# SCH.net
KiCad netlist of a schematic drawn in Altium Designer
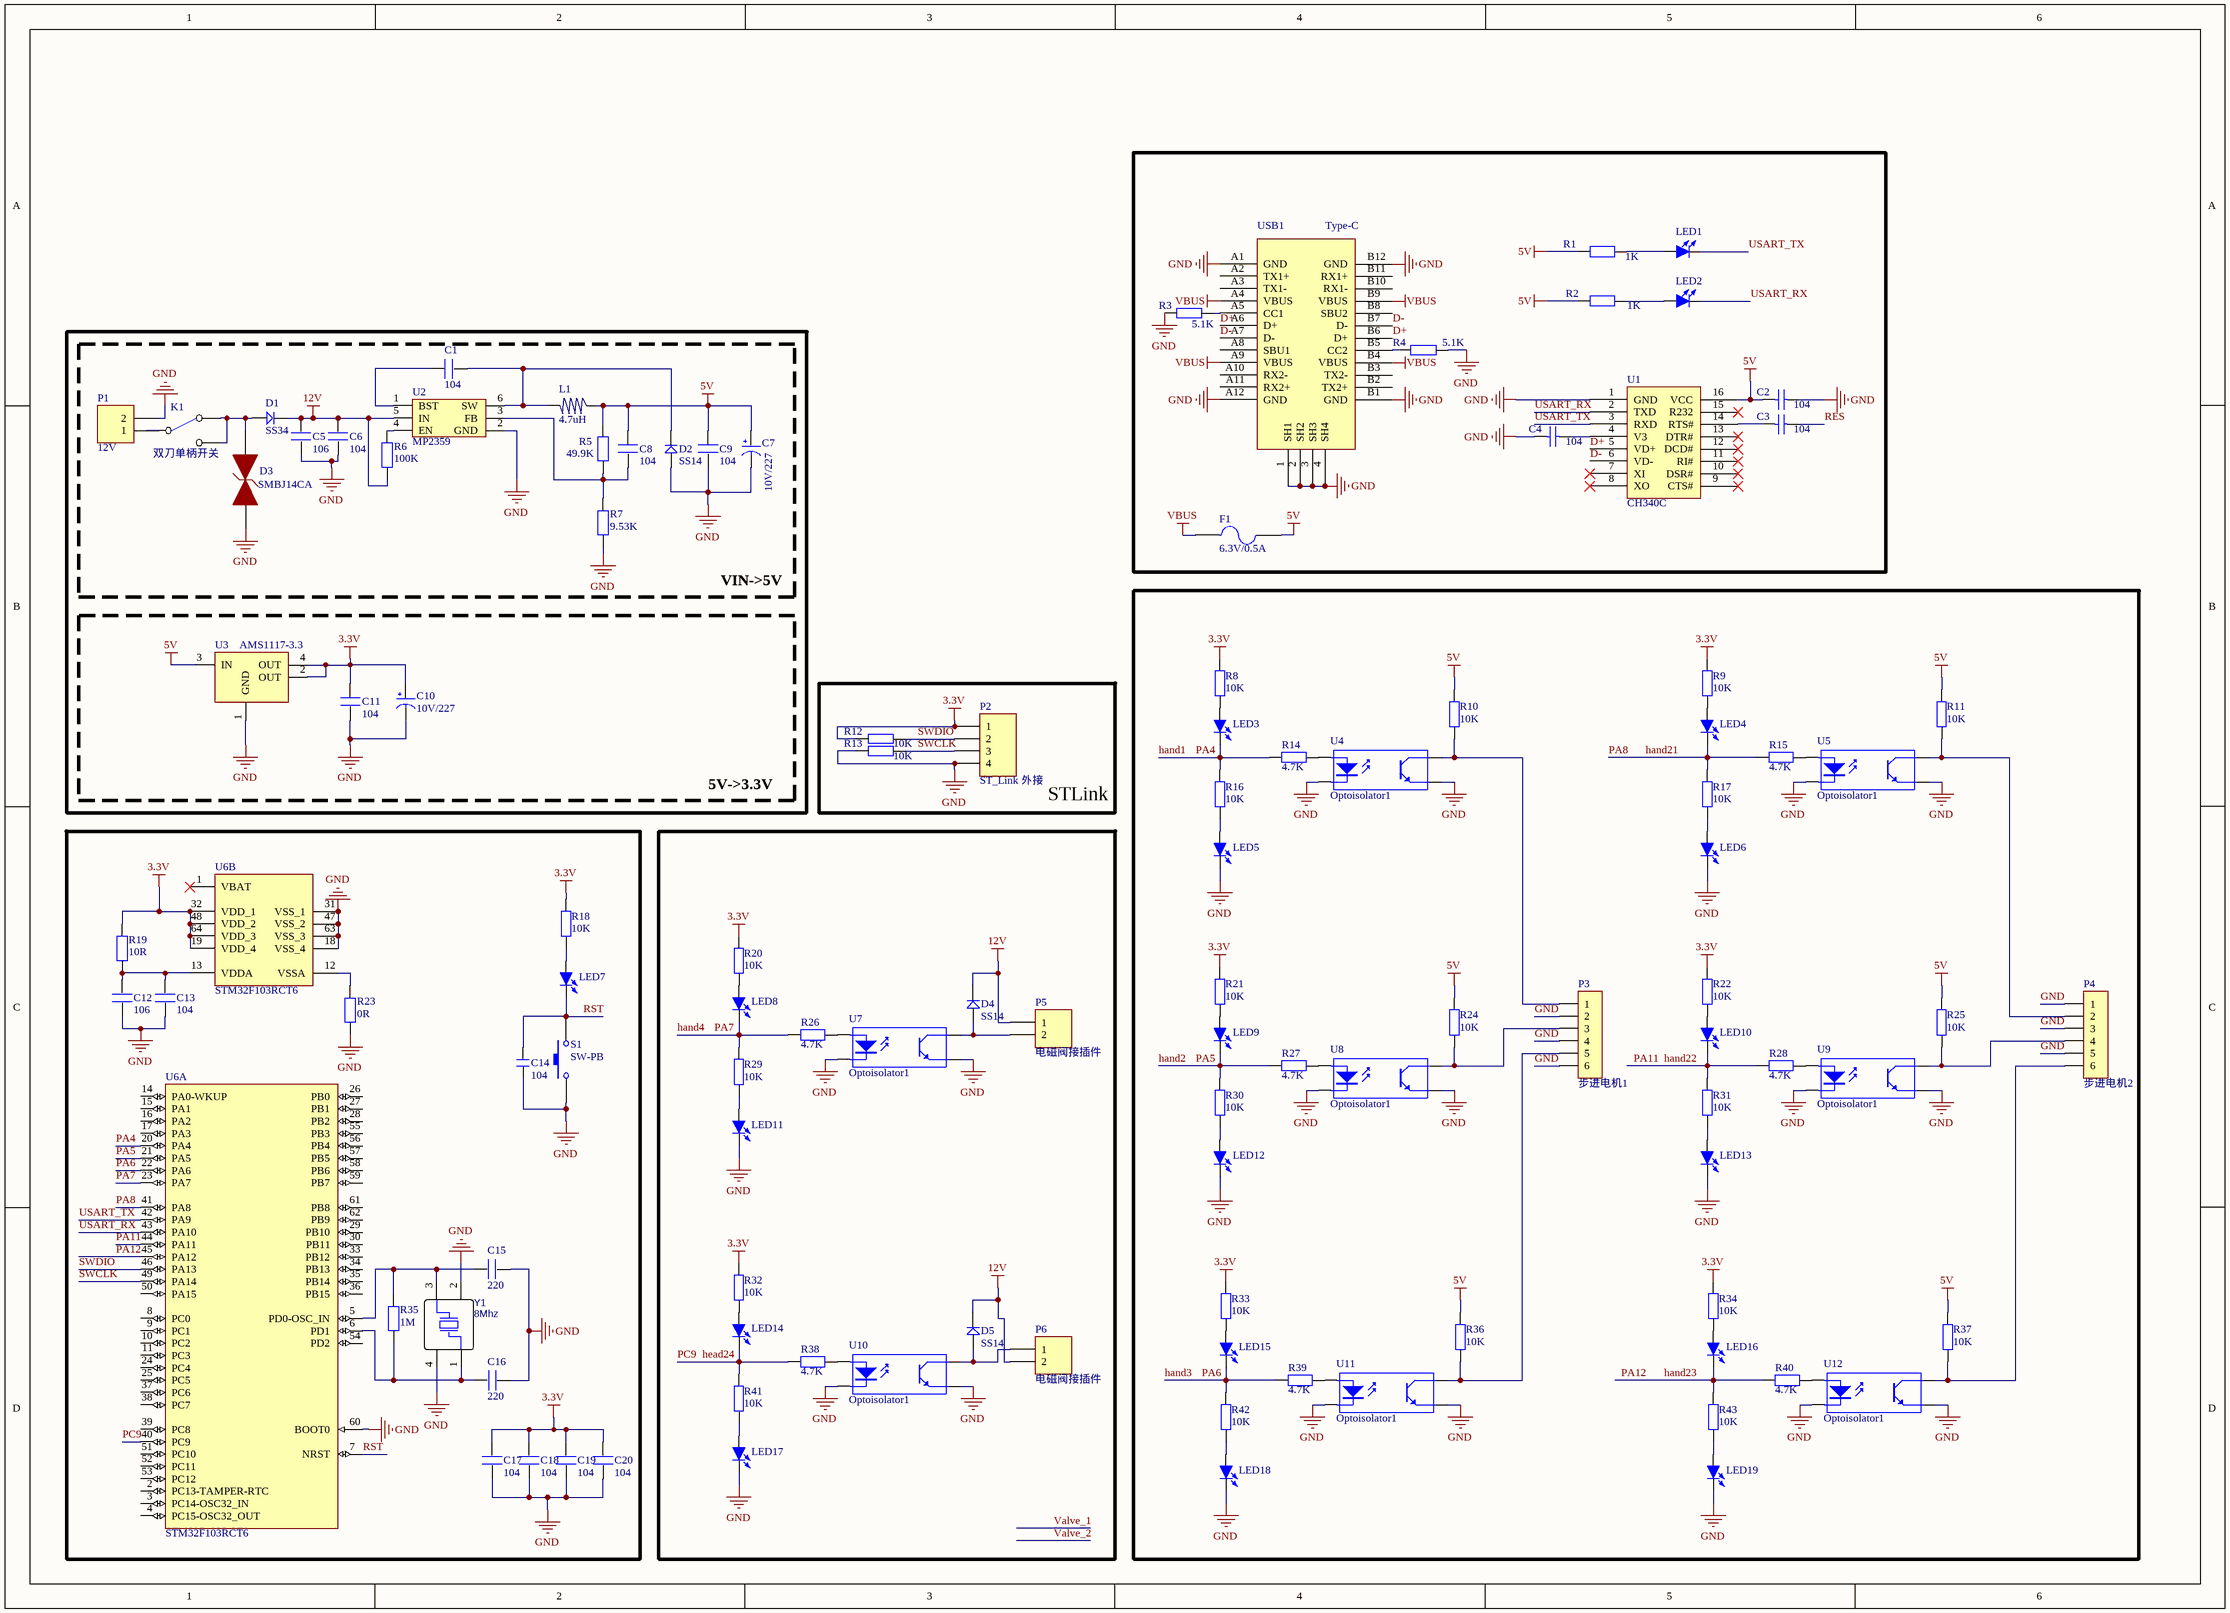
[diagram p0: SCH.SchDoc]

(export (version "E")
  (design (tool "Eeschema 10.0.6"))
  (components
    (comp (ref "C1") (value "104") (footprint "C 0805_L") (libsource (lib "EXPLORER") (part "C")))
    (comp (ref "C2")
      (value "104")
      (footprint "C 0805_L")
      (description "Capacitor")
      (fields (field (name "PUBLISHER") "Altium Limited"))
      (libsource (lib "Miscellaneous Devices") (part "Cap"))
    )
    (comp (ref "C3")
      (value "104")
      (footprint "C 0805_L")
      (description "Capacitor")
      (fields (field (name "PUBLISHER") "Altium Limited"))
      (libsource (lib "Miscellaneous Devices") (part "Cap"))
    )
    (comp (ref "C4")
      (value "104")
      (footprint "C 0805_L")
      (description "Capacitor")
      (fields (field (name "PUBLISHER") "Altium Limited"))
      (libsource (lib "Miscellaneous Devices") (part "Cap"))
    )
    (comp (ref "C5") (value "106") (footprint "C 0805_L") (libsource (lib "EXPLORER") (part "C")))
    (comp (ref "C6") (value "104") (footprint "C 0805_L") (libsource (lib "EXPLORER") (part "C")))
    (comp (ref "C7") (value "10V/227") (footprint "CM D(6.3*7.7)") (libsource (lib "EXPLORER") (part "CAP")))
    (comp (ref "C8") (value "104") (footprint "C 0805_L") (libsource (lib "EXPLORER") (part "C")))
    (comp (ref "C9") (value "104") (footprint "C 0805_L") (libsource (lib "EXPLORER") (part "C")))
    (comp (ref "C10") (value "10V/227") (footprint "CM D(6.3*7.7)") (libsource (lib "EXPLORER") (part "CAP")))
    (comp (ref "C11") (value "104") (footprint "C 0805_L") (libsource (lib "EXPLORER") (part "C")))
    (comp (ref "C12") (value "106") (footprint "C 0805_L") (libsource (lib "EXPLORER") (part "C")))
    (comp (ref "C13") (value "104") (footprint "C 0805_L") (libsource (lib "EXPLORER") (part "C")))
    (comp (ref "C14")
      (value "104")
      (footprint "C 0805_L")
      (description "贴片电容")
      (libsource (lib "0.1 - 电阻-电容-电感") (part "C"))
    )
    (comp (ref "C15") (value "220") (footprint "C 0805_L") (libsource (lib "EXPLORER") (part "C")))
    (comp (ref "C16") (value "220") (footprint "C 0805_L") (libsource (lib "EXPLORER") (part "C")))
    (comp (ref "C17") (value "104") (footprint "C 0805_L") (libsource (lib "EXPLORER") (part "C")))
    (comp (ref "C18") (value "104") (footprint "C 0805_L") (libsource (lib "EXPLORER") (part "C")))
    (comp (ref "C19") (value "104") (footprint "C 0805_L") (libsource (lib "EXPLORER") (part "C")))
    (comp (ref "C20") (value "104") (footprint "C 0805_L") (libsource (lib "EXPLORER") (part "C")))
    (comp (ref "D1") (value "SS34") (footprint "SMA") (libsource (lib "EXPLORER") (part "D")))
    (comp (ref "D2") (value "SS14") (footprint "SMA") (libsource (lib "EXPLORER") (part "D")))
    (comp (ref "D3")
      (value "SMBJ14CA")
      (footprint "SMB/DO214AA")
      (libsource (lib "MyPcbLib") (part "SMBJ28CA"))
    )
    (comp (ref "D4") (value "SS14") (footprint "SMA") (libsource (lib "EXPLORER") (part "D")))
    (comp (ref "D5") (value "SS14") (footprint "SMA") (libsource (lib "EXPLORER") (part "D")))
    (comp (ref "F1")
      (value "6.3V/0.5A")
      (footprint "C 0805_L")
      (description "Fuse")
      (fields (field (name "PUBLISHER") "Altium Limited"))
      (libsource (lib "Miscellaneous Devices") (part "Fuse 2"))
    )
    (comp (ref "K1") (value "双刀单柄开关") (footprint "SS-12D10") (libsource (lib "k-开关") (part "双刀单柄开关")))
    (comp (ref "L1") (value "4.7uH") (footprint "CDRH74") (libsource (lib "EXPLORER") (part "L")))
    (comp (ref "LED1")
      (value "~")
      (footprint "LED 0805R")
      (description "贴片LED")
      (fields (field (name "版权归属") "封装库来自淘宝 ID：黄晶宝石"))
      (libsource (lib "0.3 - LED发光二极管") (part "LED-SMD"))
    )
    (comp (ref "LED2")
      (value "~")
      (footprint "LED 0805R")
      (description "贴片LED")
      (fields (field (name "版权归属") "封装库来自淘宝 ID：黄晶宝石"))
      (libsource (lib "0.3 - LED发光二极管") (part "LED-SMD"))
    )
    (comp (ref "LED3")
      (value "~")
      (footprint "LED 0805R")
      (description "贴片LED")
      (fields (field (name "版权归属") "封装库来自淘宝 ID：黄晶宝石"))
      (libsource (lib "0.3 - LED发光二极管") (part "LED-SMD"))
    )
    (comp (ref "LED4")
      (value "~")
      (footprint "LED 0805R")
      (description "贴片LED")
      (fields (field (name "版权归属") "封装库来自淘宝 ID：黄晶宝石"))
      (libsource (lib "0.3 - LED发光二极管") (part "LED-SMD"))
    )
    (comp (ref "LED5")
      (value "~")
      (footprint "LED 0805R")
      (description "贴片LED")
      (fields (field (name "版权归属") "封装库来自淘宝 ID：黄晶宝石"))
      (libsource (lib "0.3 - LED发光二极管") (part "LED-SMD"))
    )
    (comp (ref "LED6")
      (value "~")
      (footprint "LED 0805R")
      (description "贴片LED")
      (fields (field (name "版权归属") "封装库来自淘宝 ID：黄晶宝石"))
      (libsource (lib "0.3 - LED发光二极管") (part "LED-SMD"))
    )
    (comp (ref "LED7")
      (value "~")
      (footprint "LED 0805R")
      (description "贴片LED")
      (fields (field (name "版权归属") "封装库来自淘宝 ID：黄晶宝石"))
      (libsource (lib "0.3 - LED发光二极管") (part "LED-SMD"))
    )
    (comp (ref "LED8")
      (value "~")
      (footprint "LED 0805R")
      (description "贴片LED")
      (fields (field (name "版权归属") "封装库来自淘宝 ID：黄晶宝石"))
      (libsource (lib "0.3 - LED发光二极管") (part "LED-SMD"))
    )
    (comp (ref "LED9")
      (value "~")
      (footprint "LED 0805R")
      (description "贴片LED")
      (fields (field (name "版权归属") "封装库来自淘宝 ID：黄晶宝石"))
      (libsource (lib "0.3 - LED发光二极管") (part "LED-SMD"))
    )
    (comp (ref "LED10")
      (value "~")
      (footprint "LED 0805R")
      (description "贴片LED")
      (fields (field (name "版权归属") "封装库来自淘宝 ID：黄晶宝石"))
      (libsource (lib "0.3 - LED发光二极管") (part "LED-SMD"))
    )
    (comp (ref "LED11")
      (value "~")
      (footprint "LED 0805R")
      (description "贴片LED")
      (fields (field (name "版权归属") "封装库来自淘宝 ID：黄晶宝石"))
      (libsource (lib "0.3 - LED发光二极管") (part "LED-SMD"))
    )
    (comp (ref "LED12")
      (value "~")
      (footprint "LED 0805R")
      (description "贴片LED")
      (fields (field (name "版权归属") "封装库来自淘宝 ID：黄晶宝石"))
      (libsource (lib "0.3 - LED发光二极管") (part "LED-SMD"))
    )
    (comp (ref "LED13")
      (value "~")
      (footprint "LED 0805R")
      (description "贴片LED")
      (fields (field (name "版权归属") "封装库来自淘宝 ID：黄晶宝石"))
      (libsource (lib "0.3 - LED发光二极管") (part "LED-SMD"))
    )
    (comp (ref "LED14")
      (value "~")
      (footprint "LED 0805R")
      (description "贴片LED")
      (fields (field (name "版权归属") "封装库来自淘宝 ID：黄晶宝石"))
      (libsource (lib "0.3 - LED发光二极管") (part "LED-SMD"))
    )
    (comp (ref "LED15")
      (value "~")
      (footprint "LED 0805R")
      (description "贴片LED")
      (fields (field (name "版权归属") "封装库来自淘宝 ID：黄晶宝石"))
      (libsource (lib "0.3 - LED发光二极管") (part "LED-SMD"))
    )
    (comp (ref "LED16")
      (value "~")
      (footprint "LED 0805R")
      (description "贴片LED")
      (fields (field (name "版权归属") "封装库来自淘宝 ID：黄晶宝石"))
      (libsource (lib "0.3 - LED发光二极管") (part "LED-SMD"))
    )
    (comp (ref "LED17")
      (value "~")
      (footprint "LED 0805R")
      (description "贴片LED")
      (fields (field (name "版权归属") "封装库来自淘宝 ID：黄晶宝石"))
      (libsource (lib "0.3 - LED发光二极管") (part "LED-SMD"))
    )
    (comp (ref "LED18")
      (value "~")
      (footprint "LED 0805R")
      (description "贴片LED")
      (fields (field (name "版权归属") "封装库来自淘宝 ID：黄晶宝石"))
      (libsource (lib "0.3 - LED发光二极管") (part "LED-SMD"))
    )
    (comp (ref "LED19")
      (value "~")
      (footprint "LED 0805R")
      (description "贴片LED")
      (fields (field (name "版权归属") "封装库来自淘宝 ID：黄晶宝石"))
      (libsource (lib "0.3 - LED发光二极管") (part "LED-SMD"))
    )
    (comp (ref "P1")
      (value "12V")
      (footprint "KF128-5.08-2P")
      (description "12-24V")
      (fields (field (name "PUBLISHER") "Altium Limited"))
      (libsource (lib "EXPLORER") (part "Header 2"))
    )
    (comp (ref "P2")
      (value "ST_Link 外接")
      (footprint "HDR1X4")
      (description "Header, 4-Pin")
      (fields (field (name "PUBLISHER") "Altium Limited"))
      (libsource (lib "Miscellaneous Connectors") (part "Header 4"))
    )
    (comp (ref "P3")
      (value "步进电机1")
      (footprint "KF128-5.08-6P")
      (description "6P接插件")
      (libsource (lib "18 - 接插件-脚距2.54mm (100mil) ") (part "Header 6"))
    )
    (comp (ref "P4")
      (value "步进电机2")
      (footprint "KF128-5.08-6P")
      (description "6P接插件")
      (libsource (lib "18 - 接插件-脚距2.54mm (100mil) ") (part "Header 6"))
    )
    (comp (ref "P5")
      (value "电磁阀接插件")
      (footprint "KF128-5.08-2P")
      (description "Header, 2-Pin")
      (fields (field (name "PUBLISHER") "Altium Limited"))
      (libsource (lib "Miscellaneous Connectors") (part "MHDR1X2"))
    )
    (comp (ref "P6")
      (value "电磁阀接插件")
      (footprint "KF128-5.08-2P")
      (description "Header, 2-Pin")
      (fields (field (name "PUBLISHER") "Altium Limited"))
      (libsource (lib "Miscellaneous Connectors") (part "MHDR1X2"))
    )
    (comp (ref "R1")
      (value "1K")
      (footprint "R 0805_L")
      (description "Resistor")
      (fields (field (name "PUBLISHER") "Altium Limited"))
      (libsource (lib "") (part "Res2_2"))
    )
    (comp (ref "R2")
      (value "1K")
      (footprint "R 0805_L")
      (description "Resistor")
      (fields (field (name "PUBLISHER") "Altium Limited"))
      (libsource (lib "") (part "Res2_2"))
    )
    (comp (ref "R3") (value "5.1K") (footprint "R 0805_L") (libsource (lib "EXPLORER") (part "R")))
    (comp (ref "R4") (value "5.1K") (footprint "R 0805_L") (libsource (lib "EXPLORER") (part "R")))
    (comp (ref "R5") (value "49.9K") (footprint "R 0805_L") (libsource (lib "EXPLORER") (part "R")))
    (comp (ref "R6") (value "100K") (footprint "R 0805_L") (libsource (lib "EXPLORER") (part "R")))
    (comp (ref "R7") (value "9.53K") (footprint "R 0805_L") (libsource (lib "EXPLORER") (part "R")))
    (comp (ref "R8")
      (value "10K")
      (footprint "R 0805_L")
      (description "Resistor")
      (fields (field (name "PUBLISHER") "Altium Limited"))
      (libsource (lib "") (part "Res2_1"))
    )
    (comp (ref "R9")
      (value "10K")
      (footprint "R 0805_L")
      (description "Resistor")
      (fields (field (name "PUBLISHER") "Altium Limited"))
      (libsource (lib "") (part "Res2_1"))
    )
    (comp (ref "R10")
      (value "10K")
      (footprint "R 0805_L")
      (description "Resistor")
      (fields (field (name "PUBLISHER") "Altium Limited"))
      (libsource (lib "") (part "Res2_1"))
    )
    (comp (ref "R11")
      (value "10K")
      (footprint "R 0805_L")
      (description "Resistor")
      (fields (field (name "PUBLISHER") "Altium Limited"))
      (libsource (lib "") (part "Res2_1"))
    )
    (comp (ref "R12") (value "10K") (footprint "R 0805_L") (libsource (lib "EXPLORER") (part "R")))
    (comp (ref "R13") (value "10K") (footprint "R 0805_L") (libsource (lib "EXPLORER") (part "R")))
    (comp (ref "R14")
      (value "4.7K")
      (footprint "R 0805_L")
      (description "Resistor")
      (fields (field (name "PUBLISHER") "Altium Limited"))
      (libsource (lib "Miscellaneous Devices") (part "Res2"))
    )
    (comp (ref "R15")
      (value "4.7K")
      (footprint "R 0805_L")
      (description "Resistor")
      (fields (field (name "PUBLISHER") "Altium Limited"))
      (libsource (lib "Miscellaneous Devices") (part "Res2"))
    )
    (comp (ref "R16")
      (value "10K")
      (footprint "R 0805_L")
      (description "Resistor")
      (fields (field (name "PUBLISHER") "Altium Limited"))
      (libsource (lib "") (part "Res2_1"))
    )
    (comp (ref "R17")
      (value "10K")
      (footprint "R 0805_L")
      (description "Resistor")
      (fields (field (name "PUBLISHER") "Altium Limited"))
      (libsource (lib "") (part "Res2_1"))
    )
    (comp (ref "R18")
      (value "10K")
      (footprint "R 0805_L")
      (description "Resistor")
      (fields (field (name "PUBLISHER") "Altium Limited"))
      (libsource (lib "") (part "Res2_1"))
    )
    (comp (ref "R19") (value "10R") (footprint "R 0805_L") (libsource (lib "EXPLORER") (part "R")))
    (comp (ref "R20")
      (value "10K")
      (footprint "R 0805_L")
      (description "Resistor")
      (fields (field (name "PUBLISHER") "Altium Limited"))
      (libsource (lib "") (part "Res2_1"))
    )
    (comp (ref "R21")
      (value "10K")
      (footprint "R 0805_L")
      (description "Resistor")
      (fields (field (name "PUBLISHER") "Altium Limited"))
      (libsource (lib "") (part "Res2_1"))
    )
    (comp (ref "R22")
      (value "10K")
      (footprint "R 0805_L")
      (description "Resistor")
      (fields (field (name "PUBLISHER") "Altium Limited"))
      (libsource (lib "") (part "Res2_1"))
    )
    (comp (ref "R23") (value "0R") (footprint "R 0805_L") (libsource (lib "EXPLORER") (part "R")))
    (comp (ref "R24")
      (value "10K")
      (footprint "R 0805_L")
      (description "Resistor")
      (fields (field (name "PUBLISHER") "Altium Limited"))
      (libsource (lib "") (part "Res2_1"))
    )
    (comp (ref "R25")
      (value "10K")
      (footprint "R 0805_L")
      (description "Resistor")
      (fields (field (name "PUBLISHER") "Altium Limited"))
      (libsource (lib "") (part "Res2_1"))
    )
    (comp (ref "R26")
      (value "4.7K")
      (footprint "R 0805_L")
      (description "Resistor")
      (fields (field (name "PUBLISHER") "Altium Limited"))
      (libsource (lib "Miscellaneous Devices") (part "Res2"))
    )
    (comp (ref "R27")
      (value "4.7K")
      (footprint "R 0805_L")
      (description "Resistor")
      (fields (field (name "PUBLISHER") "Altium Limited"))
      (libsource (lib "Miscellaneous Devices") (part "Res2"))
    )
    (comp (ref "R28")
      (value "4.7K")
      (footprint "R 0805_L")
      (description "Resistor")
      (fields (field (name "PUBLISHER") "Altium Limited"))
      (libsource (lib "Miscellaneous Devices") (part "Res2"))
    )
    (comp (ref "R29")
      (value "10K")
      (footprint "R 0805_L")
      (description "Resistor")
      (fields (field (name "PUBLISHER") "Altium Limited"))
      (libsource (lib "") (part "Res2_1"))
    )
    (comp (ref "R30")
      (value "10K")
      (footprint "R 0805_L")
      (description "Resistor")
      (fields (field (name "PUBLISHER") "Altium Limited"))
      (libsource (lib "") (part "Res2_1"))
    )
    (comp (ref "R31")
      (value "10K")
      (footprint "R 0805_L")
      (description "Resistor")
      (fields (field (name "PUBLISHER") "Altium Limited"))
      (libsource (lib "") (part "Res2_1"))
    )
    (comp (ref "R32")
      (value "10K")
      (footprint "R 0805_L")
      (description "Resistor")
      (fields (field (name "PUBLISHER") "Altium Limited"))
      (libsource (lib "") (part "Res2_1"))
    )
    (comp (ref "R33")
      (value "10K")
      (footprint "R 0805_L")
      (description "Resistor")
      (fields (field (name "PUBLISHER") "Altium Limited"))
      (libsource (lib "") (part "Res2_1"))
    )
    (comp (ref "R34")
      (value "10K")
      (footprint "R 0805_L")
      (description "Resistor")
      (fields (field (name "PUBLISHER") "Altium Limited"))
      (libsource (lib "") (part "Res2_1"))
    )
    (comp (ref "R35") (value "1M") (footprint "R 0805_L") (libsource (lib "EXPLORER") (part "R")))
    (comp (ref "R36")
      (value "10K")
      (footprint "R 0805_L")
      (description "Resistor")
      (fields (field (name "PUBLISHER") "Altium Limited"))
      (libsource (lib "") (part "Res2_1"))
    )
    (comp (ref "R37")
      (value "10K")
      (footprint "R 0805_L")
      (description "Resistor")
      (fields (field (name "PUBLISHER") "Altium Limited"))
      (libsource (lib "") (part "Res2_1"))
    )
    (comp (ref "R38")
      (value "4.7K")
      (footprint "R 0805_L")
      (description "Resistor")
      (fields (field (name "PUBLISHER") "Altium Limited"))
      (libsource (lib "Miscellaneous Devices") (part "Res2"))
    )
    (comp (ref "R39")
      (value "4.7K")
      (footprint "R 0805_L")
      (description "Resistor")
      (fields (field (name "PUBLISHER") "Altium Limited"))
      (libsource (lib "Miscellaneous Devices") (part "Res2"))
    )
    (comp (ref "R40")
      (value "4.7K")
      (footprint "R 0805_L")
      (description "Resistor")
      (fields (field (name "PUBLISHER") "Altium Limited"))
      (libsource (lib "Miscellaneous Devices") (part "Res2"))
    )
    (comp (ref "R41")
      (value "10K")
      (footprint "R 0805_L")
      (description "Resistor")
      (fields (field (name "PUBLISHER") "Altium Limited"))
      (libsource (lib "") (part "Res2_1"))
    )
    (comp (ref "R42")
      (value "10K")
      (footprint "R 0805_L")
      (description "Resistor")
      (fields (field (name "PUBLISHER") "Altium Limited"))
      (libsource (lib "") (part "Res2_1"))
    )
    (comp (ref "R43")
      (value "10K")
      (footprint "R 0805_L")
      (description "Resistor")
      (fields (field (name "PUBLISHER") "Altium Limited"))
      (libsource (lib "") (part "Res2_1"))
    )
    (comp (ref "S1")
      (value "SW-PB")
      (footprint "复位按键")
      (description "Switch")
      (fields (field (name "PUBLISHER") "Altium Limited"))
      (libsource (lib "Miscellaneous Devices") (part "SW-PB"))
    )
    (comp (ref "U1") (value "CH340C") (footprint "SOP16") (libsource (lib "Schlib1") (part "CH340G")))
    (comp (ref "U2")
      (value "MP2359")
      (footprint "SOT23-6L")
      (description "DC DC Step Down IC")
      (libsource (lib "EXPLORER") (part "MP2359"))
    )
    (comp (ref "U3")
      (value "AMS1117-3.3")
      (footprint "SOT223_L")
      (libsource (lib "EXPLORER") (part "AMS1117"))
    )
    (comp (ref "U4")
      (value "Optoisolator1")
      (footprint "SOP4-W2.54_M")
      (description "4-Pin Phototransistor Optocoupler")
      (fields (field (name "PUBLISHER") "Altium Limited"))
      (libsource (lib "Miscellaneous Devices") (part "Optoisolator1"))
    )
    (comp (ref "U5")
      (value "Optoisolator1")
      (footprint "SOP4-W2.54_M")
      (description "4-Pin Phototransistor Optocoupler")
      (fields (field (name "PUBLISHER") "Altium Limited"))
      (libsource (lib "Miscellaneous Devices") (part "Optoisolator1"))
    )
    (comp (ref "U6")
      (value "STM32F103RCT6")
      (footprint "LQFP64_N")
      (libsource (lib "2.3 - STM32 F1系列MCU 集成库") (part "STM32F103RCT6"))
    )
    (comp (ref "U7")
      (value "Optoisolator1")
      (footprint "SOP4-W2.54_M")
      (description "4-Pin Phototransistor Optocoupler")
      (fields (field (name "PUBLISHER") "Altium Limited"))
      (libsource (lib "Miscellaneous Devices") (part "Optoisolator1"))
    )
    (comp (ref "U8")
      (value "Optoisolator1")
      (footprint "SOP4-W2.54_M")
      (description "4-Pin Phototransistor Optocoupler")
      (fields (field (name "PUBLISHER") "Altium Limited"))
      (libsource (lib "Miscellaneous Devices") (part "Optoisolator1"))
    )
    (comp (ref "U9")
      (value "Optoisolator1")
      (footprint "SOP4-W2.54_M")
      (description "4-Pin Phototransistor Optocoupler")
      (fields (field (name "PUBLISHER") "Altium Limited"))
      (libsource (lib "Miscellaneous Devices") (part "Optoisolator1"))
    )
    (comp (ref "U10")
      (value "Optoisolator1")
      (footprint "SOP4-W2.54_M")
      (description "4-Pin Phototransistor Optocoupler")
      (fields (field (name "PUBLISHER") "Altium Limited"))
      (libsource (lib "Miscellaneous Devices") (part "Optoisolator1"))
    )
    (comp (ref "U11")
      (value "Optoisolator1")
      (footprint "SOP4-W2.54_M")
      (description "4-Pin Phototransistor Optocoupler")
      (fields (field (name "PUBLISHER") "Altium Limited"))
      (libsource (lib "Miscellaneous Devices") (part "Optoisolator1"))
    )
    (comp (ref "U12")
      (value "Optoisolator1")
      (footprint "SOP4-W2.54_M")
      (description "4-Pin Phototransistor Optocoupler")
      (fields (field (name "PUBLISHER") "Altium Limited"))
      (libsource (lib "Miscellaneous Devices") (part "Optoisolator1"))
    )
    (comp (ref "USB1")
      (value "Type-C")
      (footprint "USBTypeC-16P")
      (libsource (lib "MyPcbLib") (part "USB-Type-C-TOP"))
    )
    (comp (ref "Y1")
      (value "8Mhz")
      (footprint "OSC 5032-4P")
      (fields
        (field (name "BOM_MANUFACTURER PART") "X322516MLB4SI")
        (field (name "BOM_SUPPLIER PART") "C13738")
      )
      (libsource (lib "EXPLORER") (part "Y"))
    )
  )
  (nets
    (net (code "1") (name "/D+") (class "Default")
      (node (ref "U1") (pin "5") (pinfunction "VD+_5") (pintype "passive"))
      (node (ref "USB1") (pin "A6") (pinfunction "D+_A6") (pintype "passive"))
      (node (ref "USB1") (pin "B6") (pinfunction "D+_B6") (pintype "passive"))
    )
    (net (code "2") (name "/D-") (class "Default")
      (node (ref "U1") (pin "6") (pinfunction "VD-_6") (pintype "passive"))
      (node (ref "USB1") (pin "A7") (pinfunction "D-_A7") (pintype "passive"))
      (node (ref "USB1") (pin "B7") (pinfunction "D-_B7") (pintype "passive"))
    )
    (net (code "3") (name "/PA4") (class "Default")
      (node (ref "LED3") (pin "2") (pinfunction "K_2") (pintype "passive"))
      (node (ref "R14") (pin "1") (pinfunction "1_1") (pintype "passive"))
      (node (ref "R16") (pin "1") (pinfunction "1_1") (pintype "passive"))
      (node (ref "U6") (pin "20") (pinfunction "PA4_20") (pintype "bidirectional"))
    )
    (net (code "4") (name "/PA5") (class "Default")
      (node (ref "LED9") (pin "2") (pinfunction "K_2") (pintype "passive"))
      (node (ref "R27") (pin "1") (pinfunction "1_1") (pintype "passive"))
      (node (ref "R30") (pin "1") (pinfunction "1_1") (pintype "passive"))
      (node (ref "U6") (pin "21") (pinfunction "PA5_21") (pintype "bidirectional"))
    )
    (net (code "5") (name "/PA6") (class "Default")
      (node (ref "LED15") (pin "2") (pinfunction "K_2") (pintype "passive"))
      (node (ref "R39") (pin "1") (pinfunction "1_1") (pintype "passive"))
      (node (ref "R42") (pin "1") (pinfunction "1_1") (pintype "passive"))
      (node (ref "U6") (pin "22") (pinfunction "PA6_22") (pintype "bidirectional"))
    )
    (net (code "6") (name "/PA7") (class "Default")
      (node (ref "LED8") (pin "2") (pinfunction "K_2") (pintype "passive"))
      (node (ref "R26") (pin "1") (pinfunction "1_1") (pintype "passive"))
      (node (ref "R29") (pin "1") (pinfunction "1_1") (pintype "passive"))
      (node (ref "U6") (pin "23") (pinfunction "PA7_23") (pintype "bidirectional"))
    )
    (net (code "7") (name "/PA8") (class "Default")
      (node (ref "LED4") (pin "2") (pinfunction "K_2") (pintype "passive"))
      (node (ref "R15") (pin "1") (pinfunction "1_1") (pintype "passive"))
      (node (ref "R17") (pin "1") (pinfunction "1_1") (pintype "passive"))
      (node (ref "U6") (pin "41") (pinfunction "PA8_41") (pintype "bidirectional"))
    )
    (net (code "8") (name "/PA11") (class "Default")
      (node (ref "LED10") (pin "2") (pinfunction "K_2") (pintype "passive"))
      (node (ref "R28") (pin "1") (pinfunction "1_1") (pintype "passive"))
      (node (ref "R31") (pin "1") (pinfunction "1_1") (pintype "passive"))
      (node (ref "U6") (pin "44") (pinfunction "PA11_44") (pintype "bidirectional"))
    )
    (net (code "9") (name "/PA12") (class "Default")
      (node (ref "LED16") (pin "2") (pinfunction "K_2") (pintype "passive"))
      (node (ref "R40") (pin "1") (pinfunction "1_1") (pintype "passive"))
      (node (ref "R43") (pin "1") (pinfunction "1_1") (pintype "passive"))
      (node (ref "U6") (pin "45") (pinfunction "PA12_45") (pintype "bidirectional"))
    )
    (net (code "10") (name "/PC9") (class "Default")
      (node (ref "LED14") (pin "2") (pinfunction "K_2") (pintype "passive"))
      (node (ref "R38") (pin "1") (pinfunction "1_1") (pintype "passive"))
      (node (ref "R41") (pin "1") (pinfunction "1_1") (pintype "passive"))
      (node (ref "U6") (pin "40") (pinfunction "PC9_40") (pintype "bidirectional"))
    )
    (net (code "11") (name "/RES") (class "Default")
      (node (ref "C3") (pin "1") (pinfunction "1_1") (pintype "passive"))
    )
    (net (code "12") (name "/RST") (class "Default")
      (node (ref "C14") (pin "2") (pinfunction "2_2") (pintype "passive"))
      (node (ref "LED7") (pin "2") (pinfunction "K_2") (pintype "passive"))
      (node (ref "S1") (pin "2") (pinfunction "2_2") (pintype "passive"))
      (node (ref "U6") (pin "7") (pinfunction "NRST_7") (pintype "bidirectional"))
    )
    (net (code "13") (name "/SWCLK") (class "Default")
      (node (ref "P2") (pin "3") (pinfunction "3_3") (pintype "passive"))
      (node (ref "R13") (pin "1") (pintype "passive"))
      (node (ref "U6") (pin "49") (pinfunction "PA14_49") (pintype "bidirectional"))
    )
    (net (code "14") (name "/SWDIO") (class "Default")
      (node (ref "P2") (pin "2") (pinfunction "2_2") (pintype "passive"))
      (node (ref "R12") (pin "1") (pintype "passive"))
      (node (ref "U6") (pin "46") (pinfunction "PA13_46") (pintype "bidirectional"))
    )
    (net (code "15") (name "/USART_RX") (class "Default")
      (node (ref "LED2") (pin "2") (pinfunction "K_2") (pintype "passive"))
      (node (ref "U1") (pin "2") (pinfunction "TXD_2") (pintype "passive"))
      (node (ref "U6") (pin "43") (pinfunction "PA10_43") (pintype "bidirectional"))
    )
    (net (code "16") (name "/USART_TX") (class "Default")
      (node (ref "LED1") (pin "2") (pinfunction "K_2") (pintype "passive"))
      (node (ref "U1") (pin "3") (pinfunction "RXD_3") (pintype "passive"))
      (node (ref "U6") (pin "42") (pinfunction "PA9_42") (pintype "bidirectional"))
    )
    (net (code "19") (name "3.3V") (class "Default")
      (node (ref "C10") (pin "1") (pinfunction "VCC_1") (pintype "passive"))
      (node (ref "C11") (pin "2") (pintype "passive"))
      (node (ref "C17") (pin "2") (pintype "passive"))
      (node (ref "C18") (pin "2") (pintype "passive"))
      (node (ref "C19") (pin "2") (pintype "passive"))
      (node (ref "C20") (pin "2") (pintype "passive"))
      (node (ref "P2") (pin "1") (pinfunction "1_1") (pintype "passive"))
      (node (ref "R12") (pin "2") (pintype "passive"))
      (node (ref "R18") (pin "1") (pinfunction "1_1") (pintype "passive"))
      (node (ref "R19") (pin "2") (pintype "passive"))
      (node (ref "R20") (pin "1") (pinfunction "1_1") (pintype "passive"))
      (node (ref "R21") (pin "1") (pinfunction "1_1") (pintype "passive"))
      (node (ref "R22") (pin "1") (pinfunction "1_1") (pintype "passive"))
      (node (ref "R32") (pin "1") (pinfunction "1_1") (pintype "passive"))
      (node (ref "R33") (pin "1") (pinfunction "1_1") (pintype "passive"))
      (node (ref "R34") (pin "1") (pinfunction "1_1") (pintype "passive"))
      (node (ref "R8") (pin "1") (pinfunction "1_1") (pintype "passive"))
      (node (ref "R9") (pin "1") (pinfunction "1_1") (pintype "passive"))
      (node (ref "U3") (pin "2") (pinfunction "OUT_2") (pintype "passive"))
      (node (ref "U3") (pin "4") (pinfunction "OUT_4") (pintype "passive"))
      (node (ref "U6") (pin "19") (pinfunction "VDD_4_19") (pintype "power_in"))
      (node (ref "U6") (pin "32") (pinfunction "VDD_1_32") (pintype "power_in"))
      (node (ref "U6") (pin "48") (pinfunction "VDD_2_48") (pintype "power_in"))
      (node (ref "U6") (pin "64") (pinfunction "VDD_3_64") (pintype "power_in"))
    )
    (net (code "20") (name "5V") (class "Default")
      (node (ref "C2") (pin "2") (pinfunction "2_2") (pintype "passive"))
      (node (ref "C7") (pin "1") (pinfunction "VCC_1") (pintype "passive"))
      (node (ref "C8") (pin "2") (pintype "passive"))
      (node (ref "C9") (pin "2") (pintype "passive"))
      (node (ref "F1") (pin "2") (pinfunction "2_2") (pintype "passive"))
      (node (ref "L1") (pin "1") (pintype "passive"))
      (node (ref "R1") (pin "2") (pinfunction "2_2") (pintype "passive"))
      (node (ref "R10") (pin "1") (pinfunction "1_1") (pintype "passive"))
      (node (ref "R11") (pin "1") (pinfunction "1_1") (pintype "passive"))
      (node (ref "R2") (pin "2") (pinfunction "2_2") (pintype "passive"))
      (node (ref "R24") (pin "1") (pinfunction "1_1") (pintype "passive"))
      (node (ref "R25") (pin "1") (pinfunction "1_1") (pintype "passive"))
      (node (ref "R36") (pin "1") (pinfunction "1_1") (pintype "passive"))
      (node (ref "R37") (pin "1") (pinfunction "1_1") (pintype "passive"))
      (node (ref "R5") (pin "2") (pintype "passive"))
      (node (ref "U1") (pin "16") (pinfunction "VCC_16") (pintype "passive"))
      (node (ref "U3") (pin "3") (pinfunction "IN_3") (pintype "passive"))
    )
    (net (code "21") (name "12V") (class "Default")
      (node (ref "C5") (pin "2") (pintype "passive"))
      (node (ref "C6") (pin "2") (pintype "passive"))
      (node (ref "D1") (pin "2") (pintype "passive"))
      (node (ref "D4") (pin "2") (pintype "passive"))
      (node (ref "D5") (pin "2") (pintype "passive"))
      (node (ref "P5") (pin "1") (pinfunction "1_1") (pintype "passive"))
      (node (ref "P6") (pin "2") (pinfunction "2_2") (pintype "passive"))
      (node (ref "R6") (pin "2") (pintype "passive"))
      (node (ref "U2") (pin "5") (pinfunction "IN_5") (pintype "passive"))
    )
    (net (code "22") (name "GND") (class "Default")
      (node (ref "C10") (pin "2") (pinfunction "GND_2") (pintype "passive"))
      (node (ref "C11") (pin "1") (pintype "passive"))
      (node (ref "C12") (pin "2") (pintype "passive"))
      (node (ref "C13") (pin "2") (pintype "passive"))
      (node (ref "C14") (pin "1") (pinfunction "1_1") (pintype "passive"))
      (node (ref "C15") (pin "2") (pintype "passive"))
      (node (ref "C16") (pin "1") (pintype "passive"))
      (node (ref "C17") (pin "1") (pintype "passive"))
      (node (ref "C18") (pin "1") (pintype "passive"))
      (node (ref "C19") (pin "1") (pintype "passive"))
      (node (ref "C2") (pin "1") (pinfunction "1_1") (pintype "passive"))
      (node (ref "C20") (pin "1") (pintype "passive"))
      (node (ref "C4") (pin "2") (pinfunction "2_2") (pintype "passive"))
      (node (ref "C5") (pin "1") (pintype "passive"))
      (node (ref "C6") (pin "1") (pintype "passive"))
      (node (ref "C7") (pin "2") (pinfunction "GND_2") (pintype "passive"))
      (node (ref "C9") (pin "1") (pintype "passive"))
      (node (ref "D2") (pin "1") (pintype "passive"))
      (node (ref "D3") (pin "1") (pinfunction "1_1") (pintype "passive"))
      (node (ref "LED11") (pin "2") (pinfunction "K_2") (pintype "passive"))
      (node (ref "LED12") (pin "2") (pinfunction "K_2") (pintype "passive"))
      (node (ref "LED13") (pin "2") (pinfunction "K_2") (pintype "passive"))
      (node (ref "LED17") (pin "2") (pinfunction "K_2") (pintype "passive"))
      (node (ref "LED18") (pin "2") (pinfunction "K_2") (pintype "passive"))
      (node (ref "LED19") (pin "2") (pinfunction "K_2") (pintype "passive"))
      (node (ref "LED5") (pin "2") (pinfunction "K_2") (pintype "passive"))
      (node (ref "LED6") (pin "2") (pinfunction "K_2") (pintype "passive"))
      (node (ref "P1") (pin "2") (pinfunction "2_2") (pintype "passive"))
      (node (ref "P2") (pin "4") (pinfunction "4_4") (pintype "passive"))
      (node (ref "P3") (pin "2") (pinfunction "2_2") (pintype "passive"))
      (node (ref "P3") (pin "4") (pinfunction "4_4") (pintype "passive"))
      (node (ref "P3") (pin "6") (pinfunction "6_6") (pintype "passive"))
      (node (ref "P4") (pin "1") (pinfunction "1_1") (pintype "passive"))
      (node (ref "P4") (pin "3") (pinfunction "3_3") (pintype "passive"))
      (node (ref "P4") (pin "5") (pinfunction "5_5") (pintype "passive"))
      (node (ref "R13") (pin "2") (pintype "passive"))
      (node (ref "R23") (pin "1") (pintype "passive"))
      (node (ref "R3") (pin "1") (pintype "passive"))
      (node (ref "R4") (pin "2") (pintype "passive"))
      (node (ref "R7") (pin "1") (pintype "passive"))
      (node (ref "S1") (pin "1") (pinfunction "1_1") (pintype "passive"))
      (node (ref "U1") (pin "1") (pinfunction "GND_1") (pintype "passive"))
      (node (ref "U10") (pin "2") (pinfunction "K_2") (pintype "passive"))
      (node (ref "U10") (pin "3") (pinfunction "E_3") (pintype "passive"))
      (node (ref "U11") (pin "2") (pinfunction "K_2") (pintype "passive"))
      (node (ref "U11") (pin "3") (pinfunction "E_3") (pintype "passive"))
      (node (ref "U12") (pin "2") (pinfunction "K_2") (pintype "passive"))
      (node (ref "U12") (pin "3") (pinfunction "E_3") (pintype "passive"))
      (node (ref "U2") (pin "2") (pinfunction "GND_2") (pintype "passive"))
      (node (ref "U3") (pin "1") (pinfunction "GND_1") (pintype "passive"))
      (node (ref "U4") (pin "2") (pinfunction "K_2") (pintype "passive"))
      (node (ref "U4") (pin "3") (pinfunction "E_3") (pintype "passive"))
      (node (ref "U5") (pin "2") (pinfunction "K_2") (pintype "passive"))
      (node (ref "U5") (pin "3") (pinfunction "E_3") (pintype "passive"))
      (node (ref "U6") (pin "18") (pinfunction "VSS_4_18") (pintype "power_in"))
      (node (ref "U6") (pin "31") (pinfunction "VSS_1_31") (pintype "power_in"))
      (node (ref "U6") (pin "47") (pinfunction "VSS_2_47") (pintype "power_in"))
      (node (ref "U6") (pin "60") (pinfunction "BOOT0_60") (pintype "input"))
      (node (ref "U6") (pin "63") (pinfunction "VSS_3_63") (pintype "power_in"))
      (node (ref "U7") (pin "2") (pinfunction "K_2") (pintype "passive"))
      (node (ref "U7") (pin "3") (pinfunction "E_3") (pintype "passive"))
      (node (ref "U8") (pin "2") (pinfunction "K_2") (pintype "passive"))
      (node (ref "U8") (pin "3") (pinfunction "E_3") (pintype "passive"))
      (node (ref "U9") (pin "2") (pinfunction "K_2") (pintype "passive"))
      (node (ref "U9") (pin "3") (pinfunction "E_3") (pintype "passive"))
      (node (ref "USB1") (pin "1") (pinfunction "SH1_1") (pintype "passive"))
      (node (ref "USB1") (pin "2") (pinfunction "SH2_2") (pintype "passive"))
      (node (ref "USB1") (pin "3") (pinfunction "SH3_3") (pintype "passive"))
      (node (ref "USB1") (pin "4") (pinfunction "SH4_4") (pintype "passive"))
      (node (ref "USB1") (pin "A1") (pinfunction "GND_A1") (pintype "passive"))
      (node (ref "USB1") (pin "A12") (pinfunction "GND_A12") (pintype "passive"))
      (node (ref "USB1") (pin "B1") (pinfunction "GND_B1") (pintype "passive"))
      (node (ref "USB1") (pin "B12") (pinfunction "GND_B12") (pintype "passive"))
      (node (ref "Y1") (pin "2") (pinfunction "GND_2") (pintype "passive"))
      (node (ref "Y1") (pin "4") (pinfunction "GND_4") (pintype "passive"))
    )
    (net (code "23") (name "Net-(K1-COMMON)") (class "Default")
      (node (ref "K1") (pin "1") (pinfunction "COMMON_1") (pintype "passive"))
      (node (ref "P1") (pin "1") (pinfunction "1_1") (pintype "passive"))
    )
    (net (code "24") (name "Net-(K1-NC)") (class "Default")
      (node (ref "D1") (pin "1") (pintype "passive"))
      (node (ref "D3") (pin "2") (pinfunction "2_2") (pintype "passive"))
      (node (ref "K1") (pin "2") (pinfunction "NC_2") (pintype "passive"))
      (node (ref "K1") (pin "3") (pinfunction "NO_3") (pintype "passive"))
    )
    (net (code "25") (name "Net-(LED1-A)") (class "Default")
      (node (ref "LED1") (pin "1") (pinfunction "A_1") (pintype "passive"))
      (node (ref "R1") (pin "1") (pinfunction "1_1") (pintype "passive"))
    )
    (net (code "26") (name "Net-(LED2-A)") (class "Default")
      (node (ref "LED2") (pin "1") (pinfunction "A_1") (pintype "passive"))
      (node (ref "R2") (pin "1") (pinfunction "1_1") (pintype "passive"))
    )
    (net (code "27") (name "Net-(LED3-A)") (class "Default")
      (node (ref "LED3") (pin "1") (pinfunction "A_1") (pintype "passive"))
      (node (ref "R8") (pin "2") (pinfunction "2_2") (pintype "passive"))
    )
    (net (code "28") (name "Net-(LED4-A)") (class "Default")
      (node (ref "LED4") (pin "1") (pinfunction "A_1") (pintype "passive"))
      (node (ref "R9") (pin "2") (pinfunction "2_2") (pintype "passive"))
    )
    (net (code "29") (name "Net-(LED5-A)") (class "Default")
      (node (ref "LED5") (pin "1") (pinfunction "A_1") (pintype "passive"))
      (node (ref "R16") (pin "2") (pinfunction "2_2") (pintype "passive"))
    )
    (net (code "30") (name "Net-(LED6-A)") (class "Default")
      (node (ref "LED6") (pin "1") (pinfunction "A_1") (pintype "passive"))
      (node (ref "R17") (pin "2") (pinfunction "2_2") (pintype "passive"))
    )
    (net (code "31") (name "Net-(LED7-A)") (class "Default")
      (node (ref "LED7") (pin "1") (pinfunction "A_1") (pintype "passive"))
      (node (ref "R18") (pin "2") (pinfunction "2_2") (pintype "passive"))
    )
    (net (code "32") (name "Net-(LED8-A)") (class "Default")
      (node (ref "LED8") (pin "1") (pinfunction "A_1") (pintype "passive"))
      (node (ref "R20") (pin "2") (pinfunction "2_2") (pintype "passive"))
    )
    (net (code "33") (name "Net-(LED9-A)") (class "Default")
      (node (ref "LED9") (pin "1") (pinfunction "A_1") (pintype "passive"))
      (node (ref "R21") (pin "2") (pinfunction "2_2") (pintype "passive"))
    )
    (net (code "34") (name "Net-(LED10-A)") (class "Default")
      (node (ref "LED10") (pin "1") (pinfunction "A_1") (pintype "passive"))
      (node (ref "R22") (pin "2") (pinfunction "2_2") (pintype "passive"))
    )
    (net (code "35") (name "Net-(LED11-A)") (class "Default")
      (node (ref "LED11") (pin "1") (pinfunction "A_1") (pintype "passive"))
      (node (ref "R29") (pin "2") (pinfunction "2_2") (pintype "passive"))
    )
    (net (code "36") (name "Net-(LED12-A)") (class "Default")
      (node (ref "LED12") (pin "1") (pinfunction "A_1") (pintype "passive"))
      (node (ref "R30") (pin "2") (pinfunction "2_2") (pintype "passive"))
    )
    (net (code "37") (name "Net-(LED13-A)") (class "Default")
      (node (ref "LED13") (pin "1") (pinfunction "A_1") (pintype "passive"))
      (node (ref "R31") (pin "2") (pinfunction "2_2") (pintype "passive"))
    )
    (net (code "38") (name "Net-(LED14-A)") (class "Default")
      (node (ref "LED14") (pin "1") (pinfunction "A_1") (pintype "passive"))
      (node (ref "R32") (pin "2") (pinfunction "2_2") (pintype "passive"))
    )
    (net (code "39") (name "Net-(LED15-A)") (class "Default")
      (node (ref "LED15") (pin "1") (pinfunction "A_1") (pintype "passive"))
      (node (ref "R33") (pin "2") (pinfunction "2_2") (pintype "passive"))
    )
    (net (code "40") (name "Net-(LED16-A)") (class "Default")
      (node (ref "LED16") (pin "1") (pinfunction "A_1") (pintype "passive"))
      (node (ref "R34") (pin "2") (pinfunction "2_2") (pintype "passive"))
    )
    (net (code "41") (name "Net-(LED17-A)") (class "Default")
      (node (ref "LED17") (pin "1") (pinfunction "A_1") (pintype "passive"))
      (node (ref "R41") (pin "2") (pinfunction "2_2") (pintype "passive"))
    )
    (net (code "42") (name "Net-(LED18-A)") (class "Default")
      (node (ref "LED18") (pin "1") (pinfunction "A_1") (pintype "passive"))
      (node (ref "R42") (pin "2") (pinfunction "2_2") (pintype "passive"))
    )
    (net (code "43") (name "Net-(LED19-A)") (class "Default")
      (node (ref "LED19") (pin "1") (pinfunction "A_1") (pintype "passive"))
      (node (ref "R43") (pin "2") (pinfunction "2_2") (pintype "passive"))
    )
    (net (code "44") (name "Net-(U1-RTS#)") (class "Default")
      (node (ref "C3") (pin "2") (pinfunction "2_2") (pintype "passive"))
      (node (ref "U1") (pin "14") (pinfunction "RTS#_14") (pintype "passive"))
    )
    (net (code "45") (name "Net-(U1-V3)") (class "Default")
      (node (ref "C4") (pin "1") (pinfunction "1_1") (pintype "passive"))
      (node (ref "U1") (pin "4") (pinfunction "V3_4") (pintype "passive"))
    )
    (net (code "46") (name "Net-(U2-BST)") (class "Default")
      (node (ref "C1") (pin "1") (pintype "passive"))
      (node (ref "U2") (pin "1") (pinfunction "BST_1") (pintype "passive"))
    )
    (net (code "47") (name "Net-(U2-EN)") (class "Default")
      (node (ref "R6") (pin "1") (pintype "passive"))
      (node (ref "U2") (pin "4") (pinfunction "EN_4") (pintype "passive"))
    )
    (net (code "48") (name "Net-(U2-FB)") (class "Default")
      (node (ref "C8") (pin "1") (pintype "passive"))
      (node (ref "R5") (pin "1") (pintype "passive"))
      (node (ref "R7") (pin "2") (pintype "passive"))
      (node (ref "U2") (pin "3") (pinfunction "FB_3") (pintype "passive"))
    )
    (net (code "49") (name "Net-(U2-SW)") (class "Default")
      (node (ref "C1") (pin "2") (pintype "passive"))
      (node (ref "D2") (pin "2") (pintype "passive"))
      (node (ref "L1") (pin "2") (pintype "passive"))
      (node (ref "U2") (pin "6") (pinfunction "SW_6") (pintype "passive"))
    )
    (net (code "50") (name "Net-(U4-A)") (class "Default")
      (node (ref "R14") (pin "2") (pinfunction "2_2") (pintype "passive"))
      (node (ref "U4") (pin "1") (pinfunction "A_1") (pintype "passive"))
    )
    (net (code "51") (name "Net-(U4-C)") (class "Default")
      (node (ref "P3") (pin "1") (pinfunction "1_1") (pintype "passive"))
      (node (ref "R10") (pin "2") (pinfunction "2_2") (pintype "passive"))
      (node (ref "U4") (pin "4") (pinfunction "C_4") (pintype "passive"))
    )
    (net (code "52") (name "Net-(U5-A)") (class "Default")
      (node (ref "R15") (pin "2") (pinfunction "2_2") (pintype "passive"))
      (node (ref "U5") (pin "1") (pinfunction "A_1") (pintype "passive"))
    )
    (net (code "53") (name "Net-(U5-C)") (class "Default")
      (node (ref "P4") (pin "2") (pinfunction "2_2") (pintype "passive"))
      (node (ref "R11") (pin "2") (pinfunction "2_2") (pintype "passive"))
      (node (ref "U5") (pin "4") (pinfunction "C_4") (pintype "passive"))
    )
    (net (code "54") (name "Net-(U6A-PD0-OSC_IN)") (class "Default")
      (node (ref "C15") (pin "1") (pintype "passive"))
      (node (ref "R35") (pin "2") (pintype "passive"))
      (node (ref "U6") (pin "5") (pinfunction "PD0-OSC_IN_5") (pintype "bidirectional"))
      (node (ref "Y1") (pin "3") (pinfunction "OSC2_3") (pintype "passive"))
    )
    (net (code "55") (name "Net-(U6A-PD1)") (class "Default")
      (node (ref "C16") (pin "2") (pintype "passive"))
      (node (ref "R35") (pin "1") (pintype "passive"))
      (node (ref "U6") (pin "6") (pinfunction "PD1_6") (pintype "bidirectional"))
      (node (ref "Y1") (pin "1") (pinfunction "OSC1_1") (pintype "passive"))
    )
    (net (code "56") (name "Net-(U6B-VDDA)") (class "Default")
      (node (ref "C12") (pin "1") (pintype "passive"))
      (node (ref "C13") (pin "1") (pintype "passive"))
      (node (ref "R19") (pin "1") (pintype "passive"))
      (node (ref "U6") (pin "13") (pinfunction "VDDA_13") (pintype "power_in"))
    )
    (net (code "57") (name "Net-(U6B-VSSA)") (class "Default")
      (node (ref "R23") (pin "2") (pintype "passive"))
      (node (ref "U6") (pin "12") (pinfunction "VSSA_12") (pintype "power_in"))
    )
    (net (code "58") (name "Net-(U7-A)") (class "Default")
      (node (ref "R26") (pin "2") (pinfunction "2_2") (pintype "passive"))
      (node (ref "U7") (pin "1") (pinfunction "A_1") (pintype "passive"))
    )
    (net (code "59") (name "Net-(U7-C)") (class "Default")
      (node (ref "D4") (pin "1") (pintype "passive"))
      (node (ref "P5") (pin "2") (pinfunction "2_2") (pintype "passive"))
      (node (ref "U7") (pin "4") (pinfunction "C_4") (pintype "passive"))
    )
    (net (code "60") (name "Net-(U8-A)") (class "Default")
      (node (ref "R27") (pin "2") (pinfunction "2_2") (pintype "passive"))
      (node (ref "U8") (pin "1") (pinfunction "A_1") (pintype "passive"))
    )
    (net (code "61") (name "Net-(U8-C)") (class "Default")
      (node (ref "P3") (pin "3") (pinfunction "3_3") (pintype "passive"))
      (node (ref "R24") (pin "2") (pinfunction "2_2") (pintype "passive"))
      (node (ref "U8") (pin "4") (pinfunction "C_4") (pintype "passive"))
    )
    (net (code "62") (name "Net-(U9-A)") (class "Default")
      (node (ref "R28") (pin "2") (pinfunction "2_2") (pintype "passive"))
      (node (ref "U9") (pin "1") (pinfunction "A_1") (pintype "passive"))
    )
    (net (code "63") (name "Net-(U9-C)") (class "Default")
      (node (ref "P4") (pin "4") (pinfunction "4_4") (pintype "passive"))
      (node (ref "R25") (pin "2") (pinfunction "2_2") (pintype "passive"))
      (node (ref "U9") (pin "4") (pinfunction "C_4") (pintype "passive"))
    )
    (net (code "64") (name "Net-(U10-A)") (class "Default")
      (node (ref "R38") (pin "2") (pinfunction "2_2") (pintype "passive"))
      (node (ref "U10") (pin "1") (pinfunction "A_1") (pintype "passive"))
    )
    (net (code "65") (name "Net-(U10-C)") (class "Default")
      (node (ref "D5") (pin "1") (pintype "passive"))
      (node (ref "P6") (pin "1") (pinfunction "1_1") (pintype "passive"))
      (node (ref "U10") (pin "4") (pinfunction "C_4") (pintype "passive"))
    )
    (net (code "66") (name "Net-(U11-A)") (class "Default")
      (node (ref "R39") (pin "2") (pinfunction "2_2") (pintype "passive"))
      (node (ref "U11") (pin "1") (pinfunction "A_1") (pintype "passive"))
    )
    (net (code "67") (name "Net-(U11-C)") (class "Default")
      (node (ref "P3") (pin "5") (pinfunction "5_5") (pintype "passive"))
      (node (ref "R36") (pin "2") (pinfunction "2_2") (pintype "passive"))
      (node (ref "U11") (pin "4") (pinfunction "C_4") (pintype "passive"))
    )
    (net (code "68") (name "Net-(U12-A)") (class "Default")
      (node (ref "R40") (pin "2") (pinfunction "2_2") (pintype "passive"))
      (node (ref "U12") (pin "1") (pinfunction "A_1") (pintype "passive"))
    )
    (net (code "69") (name "Net-(U12-C)") (class "Default")
      (node (ref "P4") (pin "6") (pinfunction "6_6") (pintype "passive"))
      (node (ref "R37") (pin "2") (pinfunction "2_2") (pintype "passive"))
      (node (ref "U12") (pin "4") (pinfunction "C_4") (pintype "passive"))
    )
    (net (code "70") (name "Net-(USB1-CC1)") (class "Default")
      (node (ref "R3") (pin "2") (pintype "passive"))
      (node (ref "USB1") (pin "A5") (pinfunction "CC1_A5") (pintype "passive"))
    )
    (net (code "71") (name "Net-(USB1-CC2)") (class "Default")
      (node (ref "R4") (pin "1") (pintype "passive"))
      (node (ref "USB1") (pin "B5") (pinfunction "CC2_B5") (pintype "passive"))
    )
    (net (code "72") (name "VBUS") (class "Default")
      (node (ref "F1") (pin "1") (pinfunction "1_1") (pintype "passive"))
      (node (ref "USB1") (pin "A4") (pinfunction "VBUS_A4") (pintype "passive"))
      (node (ref "USB1") (pin "A9") (pinfunction "VBUS_A9") (pintype "passive"))
      (node (ref "USB1") (pin "B4") (pinfunction "VBUS_B4") (pintype "passive"))
      (node (ref "USB1") (pin "B9") (pinfunction "VBUS_B9") (pintype "passive"))
    )
    (net (code "73") (name "unconnected-(U1-CTS#-Pad9)") (class "Default")
      (node (ref "U1") (pin "9") (pinfunction "CTS#_9") (pintype "passive+no_connect"))
    )
    (net (code "74") (name "unconnected-(U1-DCD#-Pad12)") (class "Default")
      (node (ref "U1") (pin "12") (pinfunction "DCD#_12") (pintype "passive+no_connect"))
    )
    (net (code "75") (name "unconnected-(U1-DSR#-Pad10)") (class "Default")
      (node (ref "U1") (pin "10") (pinfunction "DSR#_10") (pintype "passive+no_connect"))
    )
    (net (code "76") (name "unconnected-(U1-DTR#-Pad13)") (class "Default")
      (node (ref "U1") (pin "13") (pinfunction "DTR#_13") (pintype "passive+no_connect"))
    )
    (net (code "77") (name "unconnected-(U1-R232-Pad15)") (class "Default")
      (node (ref "U1") (pin "15") (pinfunction "R232_15") (pintype "passive+no_connect"))
    )
    (net (code "78") (name "unconnected-(U1-RI#-Pad11)") (class "Default")
      (node (ref "U1") (pin "11") (pinfunction "RI#_11") (pintype "passive+no_connect"))
    )
    (net (code "79") (name "unconnected-(U1-XI-Pad7)") (class "Default")
      (node (ref "U1") (pin "7") (pinfunction "XI_7") (pintype "passive+no_connect"))
    )
    (net (code "80") (name "unconnected-(U1-XO-Pad8)") (class "Default")
      (node (ref "U1") (pin "8") (pinfunction "XO_8") (pintype "passive+no_connect"))
    )
    (net (code "81") (name "unconnected-(U6A-PA0-WKUP-Pad14)") (class "Default")
      (node (ref "U6") (pin "14") (pinfunction "PA0-WKUP_14") (pintype "bidirectional"))
    )
    (net (code "82") (name "unconnected-(U6A-PA1-Pad15)") (class "Default")
      (node (ref "U6") (pin "15") (pinfunction "PA1_15") (pintype "bidirectional"))
    )
    (net (code "83") (name "unconnected-(U6A-PA2-Pad16)") (class "Default")
      (node (ref "U6") (pin "16") (pinfunction "PA2_16") (pintype "bidirectional"))
    )
    (net (code "84") (name "unconnected-(U6A-PA3-Pad17)") (class "Default")
      (node (ref "U6") (pin "17") (pinfunction "PA3_17") (pintype "bidirectional"))
    )
    (net (code "85") (name "unconnected-(U6A-PA15-Pad50)") (class "Default")
      (node (ref "U6") (pin "50") (pinfunction "PA15_50") (pintype "bidirectional"))
    )
    (net (code "86") (name "unconnected-(U6A-PB0-Pad26)") (class "Default")
      (node (ref "U6") (pin "26") (pinfunction "PB0_26") (pintype "bidirectional"))
    )
    (net (code "87") (name "unconnected-(U6A-PB1-Pad27)") (class "Default")
      (node (ref "U6") (pin "27") (pinfunction "PB1_27") (pintype "bidirectional"))
    )
    (net (code "88") (name "unconnected-(U6A-PB2-Pad28)") (class "Default")
      (node (ref "U6") (pin "28") (pinfunction "PB2_28") (pintype "bidirectional"))
    )
    (net (code "89") (name "unconnected-(U6A-PB3-Pad55)") (class "Default")
      (node (ref "U6") (pin "55") (pinfunction "PB3_55") (pintype "bidirectional"))
    )
    (net (code "90") (name "unconnected-(U6A-PB4-Pad56)") (class "Default")
      (node (ref "U6") (pin "56") (pinfunction "PB4_56") (pintype "bidirectional"))
    )
    (net (code "91") (name "unconnected-(U6A-PB5-Pad57)") (class "Default")
      (node (ref "U6") (pin "57") (pinfunction "PB5_57") (pintype "bidirectional"))
    )
    (net (code "92") (name "unconnected-(U6A-PB6-Pad58)") (class "Default")
      (node (ref "U6") (pin "58") (pinfunction "PB6_58") (pintype "bidirectional"))
    )
    (net (code "93") (name "unconnected-(U6A-PB7-Pad59)") (class "Default")
      (node (ref "U6") (pin "59") (pinfunction "PB7_59") (pintype "bidirectional"))
    )
    (net (code "94") (name "unconnected-(U6A-PB8-Pad61)") (class "Default")
      (node (ref "U6") (pin "61") (pinfunction "PB8_61") (pintype "bidirectional"))
    )
    (net (code "95") (name "unconnected-(U6A-PB9-Pad62)") (class "Default")
      (node (ref "U6") (pin "62") (pinfunction "PB9_62") (pintype "bidirectional"))
    )
    (net (code "96") (name "unconnected-(U6A-PB10-Pad29)") (class "Default")
      (node (ref "U6") (pin "29") (pinfunction "PB10_29") (pintype "bidirectional"))
    )
    (net (code "97") (name "unconnected-(U6A-PB11-Pad30)") (class "Default")
      (node (ref "U6") (pin "30") (pinfunction "PB11_30") (pintype "bidirectional"))
    )
    (net (code "98") (name "unconnected-(U6A-PB12-Pad33)") (class "Default")
      (node (ref "U6") (pin "33") (pinfunction "PB12_33") (pintype "bidirectional"))
    )
    (net (code "99") (name "unconnected-(U6A-PB13-Pad34)") (class "Default")
      (node (ref "U6") (pin "34") (pinfunction "PB13_34") (pintype "bidirectional"))
    )
    (net (code "100") (name "unconnected-(U6A-PB14-Pad35)") (class "Default")
      (node (ref "U6") (pin "35") (pinfunction "PB14_35") (pintype "bidirectional"))
    )
    (net (code "101") (name "unconnected-(U6A-PB15-Pad36)") (class "Default")
      (node (ref "U6") (pin "36") (pinfunction "PB15_36") (pintype "bidirectional"))
    )
    (net (code "102") (name "unconnected-(U6A-PC0-Pad8)") (class "Default")
      (node (ref "U6") (pin "8") (pinfunction "PC0_8") (pintype "bidirectional"))
    )
    (net (code "103") (name "unconnected-(U6A-PC1-Pad9)") (class "Default")
      (node (ref "U6") (pin "9") (pinfunction "PC1_9") (pintype "bidirectional"))
    )
    (net (code "104") (name "unconnected-(U6A-PC2-Pad10)") (class "Default")
      (node (ref "U6") (pin "10") (pinfunction "PC2_10") (pintype "bidirectional"))
    )
    (net (code "105") (name "unconnected-(U6A-PC3-Pad11)") (class "Default")
      (node (ref "U6") (pin "11") (pinfunction "PC3_11") (pintype "bidirectional"))
    )
    (net (code "106") (name "unconnected-(U6A-PC4-Pad24)") (class "Default")
      (node (ref "U6") (pin "24") (pinfunction "PC4_24") (pintype "bidirectional"))
    )
    (net (code "107") (name "unconnected-(U6A-PC5-Pad25)") (class "Default")
      (node (ref "U6") (pin "25") (pinfunction "PC5_25") (pintype "bidirectional"))
    )
    (net (code "108") (name "unconnected-(U6A-PC6-Pad37)") (class "Default")
      (node (ref "U6") (pin "37") (pinfunction "PC6_37") (pintype "bidirectional"))
    )
    (net (code "109") (name "unconnected-(U6A-PC7-Pad38)") (class "Default")
      (node (ref "U6") (pin "38") (pinfunction "PC7_38") (pintype "bidirectional"))
    )
    (net (code "110") (name "unconnected-(U6A-PC8-Pad39)") (class "Default")
      (node (ref "U6") (pin "39") (pinfunction "PC8_39") (pintype "bidirectional"))
    )
    (net (code "111") (name "unconnected-(U6A-PC10-Pad51)") (class "Default")
      (node (ref "U6") (pin "51") (pinfunction "PC10_51") (pintype "bidirectional"))
    )
    (net (code "112") (name "unconnected-(U6A-PC11-Pad52)") (class "Default")
      (node (ref "U6") (pin "52") (pinfunction "PC11_52") (pintype "bidirectional"))
    )
    (net (code "113") (name "unconnected-(U6A-PC12-Pad53)") (class "Default")
      (node (ref "U6") (pin "53") (pinfunction "PC12_53") (pintype "bidirectional"))
    )
    (net (code "114") (name "unconnected-(U6A-PC13-TAMPER-RTC-Pad2)") (class "Default")
      (node (ref "U6") (pin "2") (pinfunction "PC13-TAMPER-RTC_2") (pintype "bidirectional"))
    )
    (net (code "115") (name "unconnected-(U6A-PC14-OSC32_IN-Pad3)") (class "Default")
      (node (ref "U6") (pin "3") (pinfunction "PC14-OSC32_IN_3") (pintype "bidirectional"))
    )
    (net (code "116") (name "unconnected-(U6A-PC15-OSC32_OUT-Pad4)") (class "Default")
      (node (ref "U6") (pin "4") (pinfunction "PC15-OSC32_OUT_4") (pintype "bidirectional"))
    )
    (net (code "117") (name "unconnected-(U6A-PD2-Pad54)") (class "Default")
      (node (ref "U6") (pin "54") (pinfunction "PD2_54") (pintype "bidirectional"))
    )
    (net (code "118") (name "unconnected-(U6B-VBAT-Pad1)") (class "Default")
      (node (ref "U6") (pin "1") (pinfunction "VBAT_1") (pintype "power_in+no_connect"))
    )
    (net (code "119") (name "unconnected-(USB1-RX1+-PadB11)") (class "Default")
      (node (ref "USB1") (pin "B11") (pinfunction "RX1+_B11") (pintype "passive"))
    )
    (net (code "120") (name "unconnected-(USB1-RX1--PadB10)") (class "Default")
      (node (ref "USB1") (pin "B10") (pinfunction "RX1-_B10") (pintype "passive"))
    )
    (net (code "121") (name "unconnected-(USB1-RX2+-PadA11)") (class "Default")
      (node (ref "USB1") (pin "A11") (pinfunction "RX2+_A11") (pintype "passive"))
    )
    (net (code "122") (name "unconnected-(USB1-RX2--PadA10)") (class "Default")
      (node (ref "USB1") (pin "A10") (pinfunction "RX2-_A10") (pintype "passive"))
    )
    (net (code "123") (name "unconnected-(USB1-SBU1-PadA8)") (class "Default")
      (node (ref "USB1") (pin "A8") (pinfunction "SBU1_A8") (pintype "passive"))
    )
    (net (code "124") (name "unconnected-(USB1-SBU2-PadB8)") (class "Default")
      (node (ref "USB1") (pin "B8") (pinfunction "SBU2_B8") (pintype "passive"))
    )
    (net (code "125") (name "unconnected-(USB1-TX1+-PadA2)") (class "Default")
      (node (ref "USB1") (pin "A2") (pinfunction "TX1+_A2") (pintype "passive"))
    )
    (net (code "126") (name "unconnected-(USB1-TX1--PadA3)") (class "Default")
      (node (ref "USB1") (pin "A3") (pinfunction "TX1-_A3") (pintype "passive"))
    )
    (net (code "127") (name "unconnected-(USB1-TX2+-PadB2)") (class "Default")
      (node (ref "USB1") (pin "B2") (pinfunction "TX2+_B2") (pintype "passive"))
    )
    (net (code "128") (name "unconnected-(USB1-TX2--PadB3)") (class "Default")
      (node (ref "USB1") (pin "B3") (pinfunction "TX2-_B3") (pintype "passive"))
    )
  )
)
